# converter.net
KiCad netlist of a schematic drawn in EAGLE
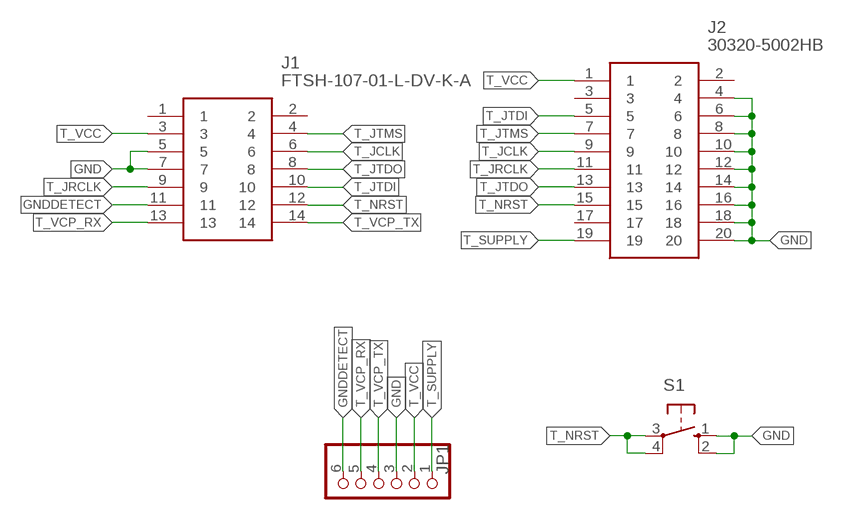
[diagram p0: schematic, sheet 1]

(export (version "E")
  (design (tool "Eeschema 10.0.6"))
  (components
    (comp (ref "J1")
      (value "FTSH-107-01-L-DV-K-A")
      (footprint "eagle-import:FTSH10701LDVKA")
      (fields (field (name "MOUSER_PART_NUMBER") "200-FTSH10701LDVKA"))
      (libsource (lib "eagle-import") (part "FTSH-107-01-L-DV-K-A"))
    )
    (comp (ref "J2")
      (value "30320-5002HB")
      (footprint "eagle-import:303205002HB")
      (fields (field (name "MOUSER_PART_NUMBER") "517-30320-5002"))
      (libsource (lib "eagle-import") (part "30320-5002HB"))
    )
    (comp (ref "JP1")
      (value "PINHD-1X6")
      (footprint "eagle-import:1X06")
      (libsource (lib "eagle-import") (part "PINHD-1X6"))
    )
    (comp (ref "S1")
      (value "10-XX")
      (footprint "eagle-import:B3F-10XX")
      (fields (field (name "MPN") "B3F-1000"))
      (libsource (lib "eagle-import") (part "10-XX"))
    )
  )
  (nets
    (net (code "1") (name "GND") (class "Default")
      (node (ref "J1") (pin "5") (pinfunction "5_5") (pintype "bidirectional"))
      (node (ref "J1") (pin "7") (pinfunction "7_7") (pintype "bidirectional"))
      (node (ref "J2") (pin "10") (pinfunction "10_10") (pintype "bidirectional"))
      (node (ref "J2") (pin "12") (pinfunction "12_12") (pintype "bidirectional"))
      (node (ref "J2") (pin "14") (pinfunction "14_14") (pintype "bidirectional"))
      (node (ref "J2") (pin "16") (pinfunction "16_16") (pintype "bidirectional"))
      (node (ref "J2") (pin "18") (pinfunction "18_18") (pintype "bidirectional"))
      (node (ref "J2") (pin "20") (pinfunction "20_20") (pintype "bidirectional"))
      (node (ref "J2") (pin "4") (pinfunction "4_4") (pintype "bidirectional"))
      (node (ref "J2") (pin "6") (pinfunction "6_6") (pintype "bidirectional"))
      (node (ref "J2") (pin "8") (pinfunction "8_8") (pintype "bidirectional"))
      (node (ref "JP1") (pin "3") (pinfunction "3_3") (pintype "passive"))
      (node (ref "S1") (pin "1") (pinfunction "S_1") (pintype "passive"))
      (node (ref "S1") (pin "2") (pinfunction "S1_2") (pintype "passive"))
    )
    (net (code "2") (name "GNDDETECT") (class "Default")
      (node (ref "J1") (pin "11") (pinfunction "11_11") (pintype "bidirectional"))
      (node (ref "JP1") (pin "6") (pinfunction "6_6") (pintype "passive"))
    )
    (net (code "3") (name "T_JCLK") (class "Default")
      (node (ref "J1") (pin "6") (pinfunction "6_6") (pintype "bidirectional"))
      (node (ref "J2") (pin "9") (pinfunction "9_9") (pintype "bidirectional"))
    )
    (net (code "4") (name "T_JRCLK") (class "Default")
      (node (ref "J1") (pin "9") (pinfunction "9_9") (pintype "bidirectional"))
      (node (ref "J2") (pin "11") (pinfunction "11_11") (pintype "bidirectional"))
    )
    (net (code "5") (name "T_JTDI") (class "Default")
      (node (ref "J1") (pin "10") (pinfunction "10_10") (pintype "bidirectional"))
      (node (ref "J2") (pin "5") (pinfunction "5_5") (pintype "bidirectional"))
    )
    (net (code "6") (name "T_JTDO") (class "Default")
      (node (ref "J1") (pin "8") (pinfunction "8_8") (pintype "bidirectional"))
      (node (ref "J2") (pin "13") (pinfunction "13_13") (pintype "bidirectional"))
    )
    (net (code "7") (name "T_JTMS") (class "Default")
      (node (ref "J1") (pin "4") (pinfunction "4_4") (pintype "bidirectional"))
      (node (ref "J2") (pin "7") (pinfunction "7_7") (pintype "bidirectional"))
    )
    (net (code "8") (name "T_NRST") (class "Default")
      (node (ref "J1") (pin "12") (pinfunction "12_12") (pintype "bidirectional"))
      (node (ref "J2") (pin "15") (pinfunction "15_15") (pintype "bidirectional"))
      (node (ref "S1") (pin "3") (pinfunction "P_3") (pintype "passive"))
      (node (ref "S1") (pin "4") (pinfunction "P1_4") (pintype "passive"))
    )
    (net (code "9") (name "T_SUPPLY") (class "Default")
      (node (ref "J2") (pin "19") (pinfunction "19_19") (pintype "bidirectional"))
      (node (ref "JP1") (pin "1") (pinfunction "1_1") (pintype "passive"))
    )
    (net (code "10") (name "T_VCC") (class "Default")
      (node (ref "J1") (pin "3") (pinfunction "3_3") (pintype "bidirectional"))
      (node (ref "J2") (pin "1") (pinfunction "1_1") (pintype "bidirectional"))
      (node (ref "JP1") (pin "2") (pinfunction "2_2") (pintype "passive"))
    )
    (net (code "11") (name "T_VCP_RX") (class "Default")
      (node (ref "J1") (pin "13") (pinfunction "13_13") (pintype "bidirectional"))
      (node (ref "JP1") (pin "5") (pinfunction "5_5") (pintype "passive"))
    )
    (net (code "12") (name "T_VCP_TX") (class "Default")
      (node (ref "J1") (pin "14") (pinfunction "14_14") (pintype "bidirectional"))
      (node (ref "JP1") (pin "4") (pinfunction "4_4") (pintype "passive"))
    )
    (net (code "13") (name "unconnected-(J1-Pad1)") (class "Default")
      (node (ref "J1") (pin "1") (pinfunction "1_1") (pintype "bidirectional"))
    )
    (net (code "14") (name "unconnected-(J1-Pad2)") (class "Default")
      (node (ref "J1") (pin "2") (pinfunction "2_2") (pintype "bidirectional"))
    )
    (net (code "15") (name "unconnected-(J2-Pad2)") (class "Default")
      (node (ref "J2") (pin "2") (pinfunction "2_2") (pintype "bidirectional"))
    )
    (net (code "16") (name "unconnected-(J2-Pad3)") (class "Default")
      (node (ref "J2") (pin "3") (pinfunction "3_3") (pintype "bidirectional"))
    )
    (net (code "17") (name "unconnected-(J2-Pad17)") (class "Default")
      (node (ref "J2") (pin "17") (pinfunction "17_17") (pintype "bidirectional"))
    )
  )
)
